# midi_block_R2_0.net
KiCad netlist of a schematic drawn in EAGLE
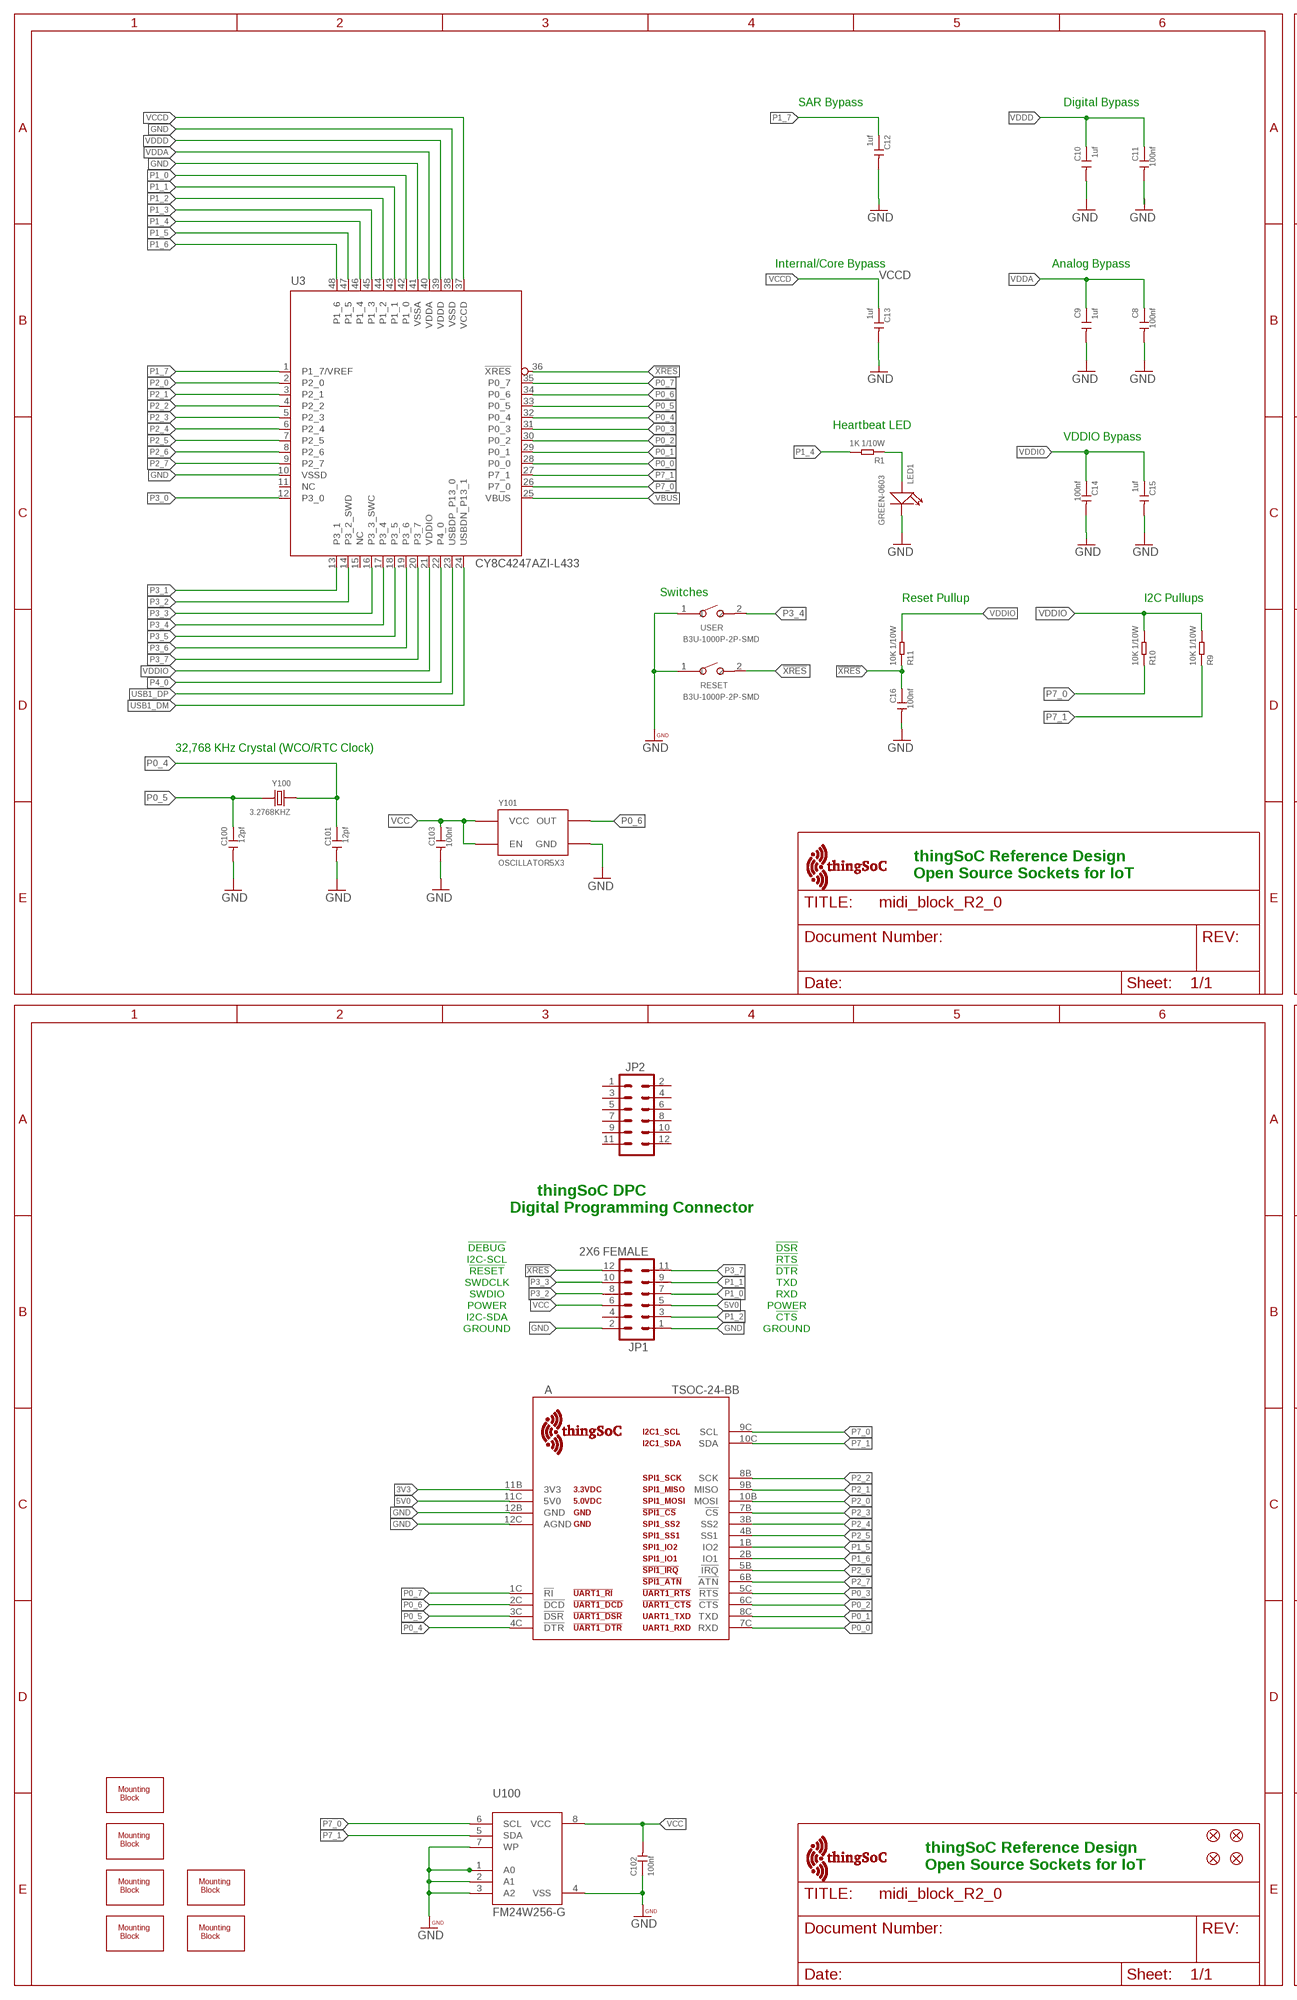
[diagram p0: schematic, sheet 1, part 1 of 2]
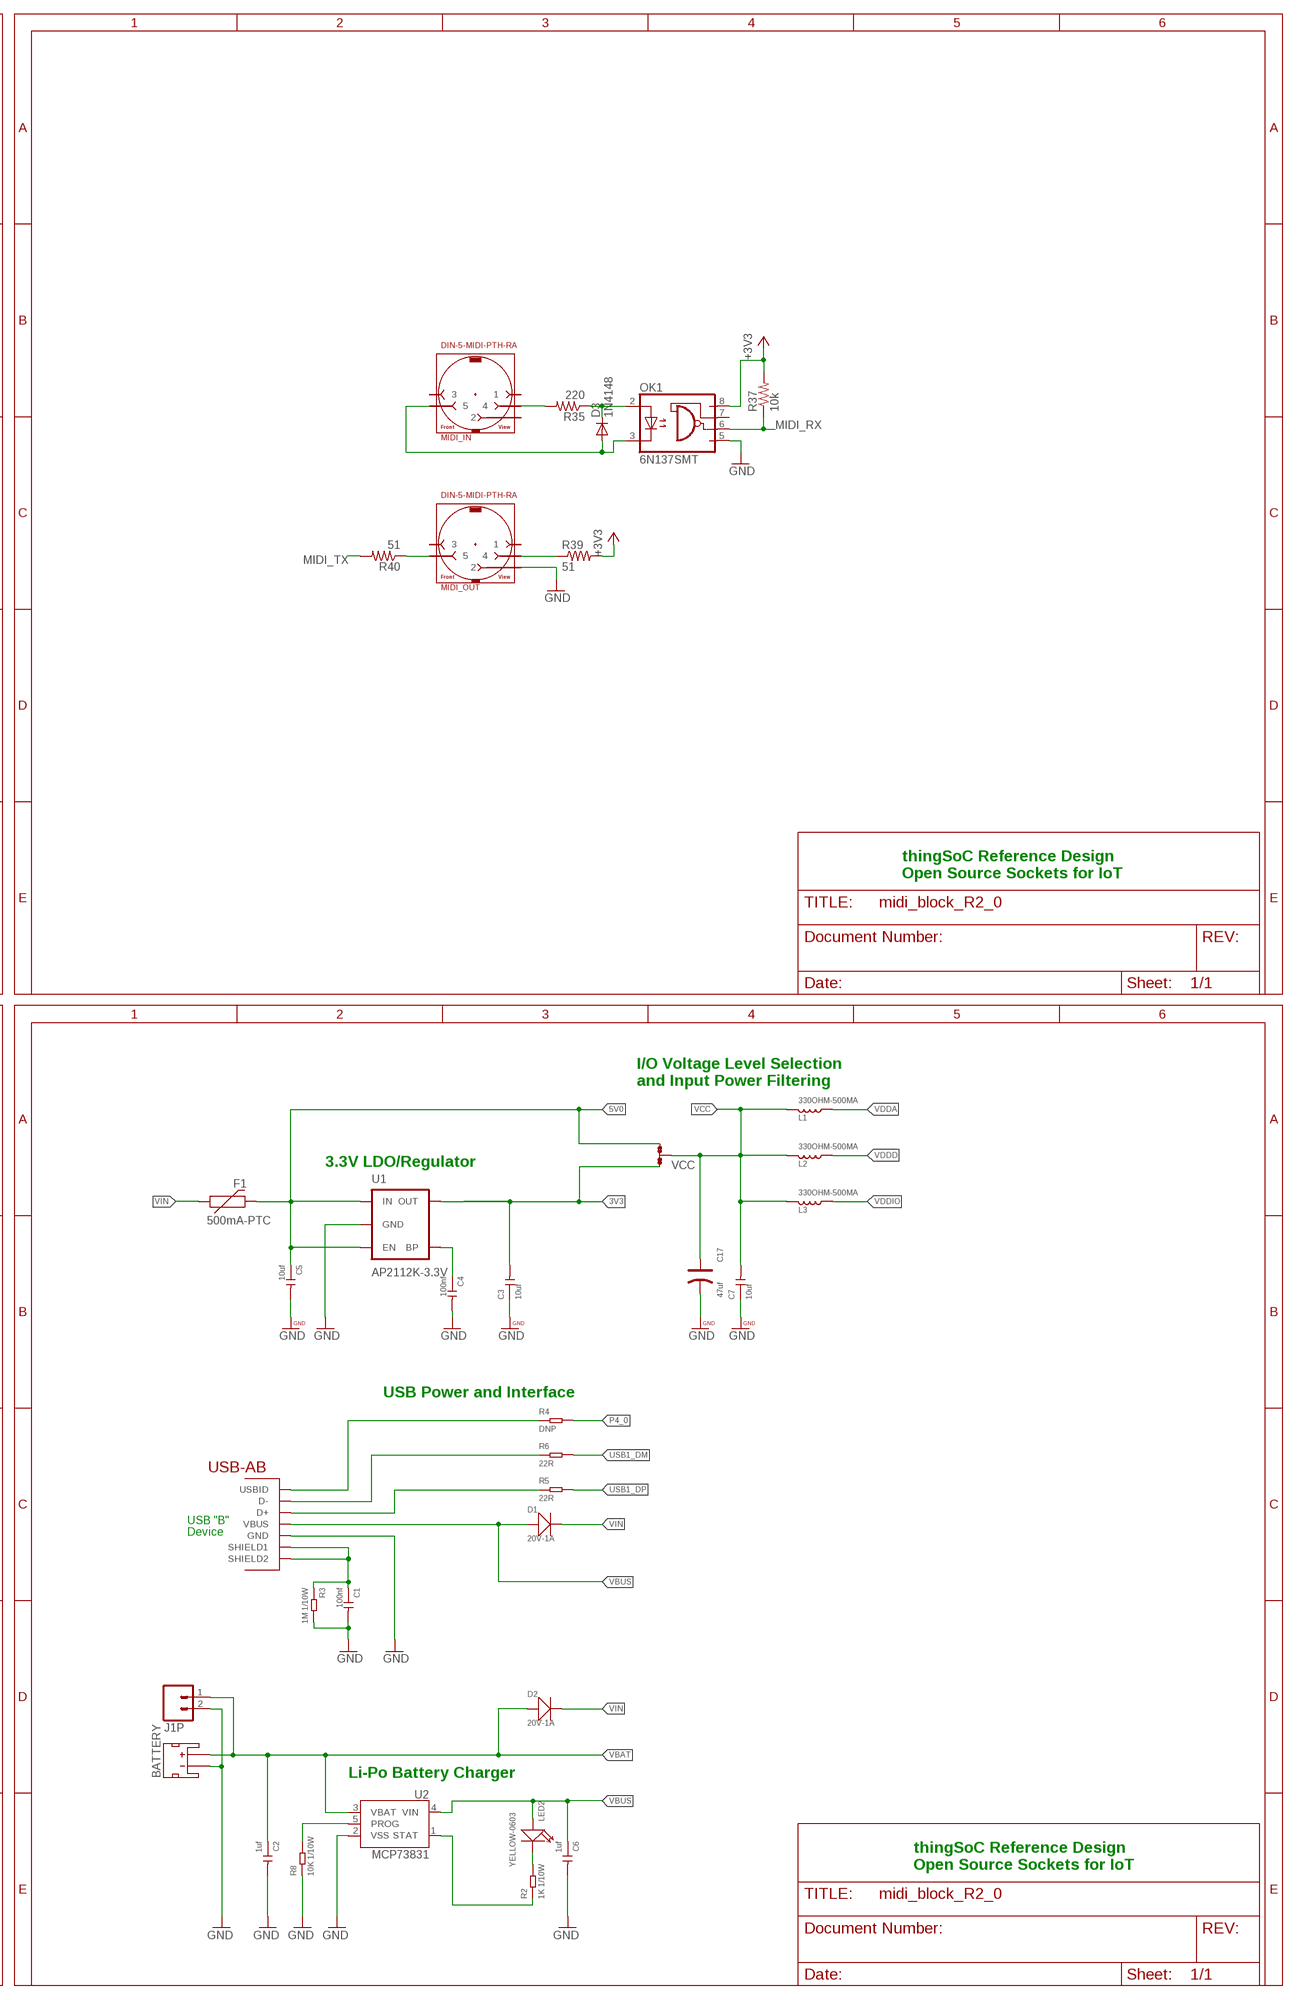
[diagram p1: schematic, sheet 1, part 2 of 2]

(export (version "E")
  (design (tool "Eeschema 10.0.6"))
  (components
    (comp (ref "A")
      (value "TSOC-24-BB")
      (footprint "eagle-import:TSOC-BB-S24")
      (libsource (lib "eagle-import") (part "TSOC-24-BB"))
    )
    (comp (ref "BATTERY")
      (value "JST_2MM_MALE")
      (footprint "eagle-import:JST-2-SMD")
      (libsource (lib "eagle-import") (part "JST_2MM_MALE"))
    )
    (comp (ref "C1")
      (value "100nf")
      (footprint "eagle-import:C0603")
      (fields (field (name "MPN") "CC0603KRX7R9BB104"))
      (libsource (lib "eagle-import") (part "CERAMIC-100NF-50V-10%-X7R(0603)"))
    )
    (comp (ref "C2")
      (value "1uf")
      (footprint "eagle-import:C0603")
      (fields (field (name "MPN") "CC0603KRX7R8BB105"))
      (libsource (lib "eagle-import") (part "CERAMIC-1UF-25V-10%-X7R(0603)"))
    )
    (comp (ref "C3")
      (value "10uf")
      (footprint "eagle-import:C0603")
      (fields (field (name "MPN") "CC0603KRX5R6BB106"))
      (libsource (lib "eagle-import") (part "CERAMIC-10UF-10V-10%-X5R(0603)"))
    )
    (comp (ref "C4")
      (value "100nf")
      (footprint "eagle-import:C0603")
      (fields (field (name "MPN") "CC0603KRX7R9BB104"))
      (libsource (lib "eagle-import") (part "CERAMIC-100NF-50V-10%-X7R(0603)"))
    )
    (comp (ref "C5")
      (value "10uf")
      (footprint "eagle-import:C0603")
      (fields (field (name "MPN") "CC0603KRX5R6BB106"))
      (libsource (lib "eagle-import") (part "CERAMIC-10UF-10V-10%-X5R(0603)"))
    )
    (comp (ref "C6")
      (value "1uf")
      (footprint "eagle-import:C0603")
      (fields (field (name "MPN") "CC0603KRX7R8BB105"))
      (libsource (lib "eagle-import") (part "CERAMIC-1UF-25V-10%-X7R(0603)"))
    )
    (comp (ref "C7")
      (value "10uf")
      (footprint "eagle-import:C0603")
      (fields (field (name "MPN") "CC0603KRX5R6BB106"))
      (libsource (lib "eagle-import") (part "CERAMIC-10UF-10V-10%-X5R(0603)"))
    )
    (comp (ref "C8")
      (value "100nf")
      (footprint "eagle-import:C0603")
      (fields (field (name "MPN") "CC0603KRX7R9BB104"))
      (libsource (lib "eagle-import") (part "CERAMIC-100NF-50V-10%-X7R(0603)"))
    )
    (comp (ref "C9")
      (value "1uf")
      (footprint "eagle-import:C0603")
      (fields (field (name "MPN") "CC0603KRX7R8BB105"))
      (libsource (lib "eagle-import") (part "CERAMIC-1UF-25V-10%-X7R(0603)"))
    )
    (comp (ref "C10")
      (value "1uf")
      (footprint "eagle-import:C0603")
      (fields (field (name "MPN") "CC0603KRX7R8BB105"))
      (libsource (lib "eagle-import") (part "CERAMIC-1UF-25V-10%-X7R(0603)"))
    )
    (comp (ref "C11")
      (value "100nf")
      (footprint "eagle-import:C0603")
      (fields (field (name "MPN") "CC0603KRX7R9BB104"))
      (libsource (lib "eagle-import") (part "CERAMIC-100NF-50V-10%-X7R(0603)"))
    )
    (comp (ref "C12")
      (value "1uf")
      (footprint "eagle-import:C0603")
      (fields (field (name "MPN") "CC0603KRX7R8BB105"))
      (libsource (lib "eagle-import") (part "CERAMIC-1UF-25V-10%-X7R(0603)"))
    )
    (comp (ref "C13")
      (value "1uf")
      (footprint "eagle-import:C0603")
      (fields (field (name "MPN") "CC0603KRX7R8BB105"))
      (libsource (lib "eagle-import") (part "CERAMIC-1UF-25V-10%-X7R(0603)"))
    )
    (comp (ref "C14")
      (value "100nf")
      (footprint "eagle-import:C0603")
      (fields (field (name "MPN") "CC0603KRX7R9BB104"))
      (libsource (lib "eagle-import") (part "CERAMIC-100NF-50V-10%-X7R(0603)"))
    )
    (comp (ref "C15")
      (value "1uf")
      (footprint "eagle-import:C0603")
      (fields (field (name "MPN") "CC0603KRX7R8BB105"))
      (libsource (lib "eagle-import") (part "CERAMIC-1UF-25V-10%-X7R(0603)"))
    )
    (comp (ref "C16")
      (value "100nf")
      (footprint "eagle-import:C0603")
      (fields (field (name "MPN") "CC0603KRX7R9BB104"))
      (libsource (lib "eagle-import") (part "CERAMIC-100NF-50V-10%-X7R(0603)"))
    )
    (comp (ref "C17")
      (value "47uf")
      (footprint "eagle-import:AVX-A")
      (fields (field (name "MPN") "TAJA476*006#NJ"))
      (libsource (lib "eagle-import") (part "TANTALUM-SMD-47UF-6.3V(AVX-A)"))
    )
    (comp (ref "C100")
      (value "12pf")
      (footprint "eagle-import:C0603")
      (fields (field (name "MPN") "CC0603JRNPO9BN120"))
      (libsource (lib "eagle-import") (part "CERAMIC-12PF-50V-5%-NPO(0603)"))
    )
    (comp (ref "C101")
      (value "12pf")
      (footprint "eagle-import:C0603")
      (fields (field (name "MPN") "CC0603JRNPO9BN120"))
      (libsource (lib "eagle-import") (part "CERAMIC-12PF-50V-5%-NPO(0603)"))
    )
    (comp (ref "C102")
      (value "100nf")
      (footprint "eagle-import:C0603")
      (fields (field (name "MPN") "CC0603KRX7R9BB104"))
      (libsource (lib "eagle-import") (part "CERAMIC-100NF-50V-10%-X7R(0603)"))
    )
    (comp (ref "C103")
      (value "100nf")
      (footprint "eagle-import:C0603")
      (fields (field (name "MPN") "CC0603KRX7R9BB104"))
      (libsource (lib "eagle-import") (part "CERAMIC-100NF-50V-10%-X7R(0603)"))
    )
    (comp (ref "D1")
      (value "20V-1A")
      (footprint "eagle-import:SOD-123")
      (fields (field (name "MPN") "B5819W"))
      (libsource (lib "eagle-import") (part "SMD-DIODE-SCHOTTKY-20V-1A(SOD-123)"))
    )
    (comp (ref "D2")
      (value "20V-1A")
      (footprint "eagle-import:SOD-123")
      (fields (field (name "MPN") "B5819W"))
      (libsource (lib "eagle-import") (part "SMD-DIODE-SCHOTTKY-20V-1A(SOD-123)"))
    )
    (comp (ref "D3")
      (value "1N4148")
      (footprint "eagle-import:SOD323-W")
      (libsource (lib "eagle-import") (part "DIODE-SOD323-W"))
    )
    (comp (ref "F1")
      (value "500mA-PTC")
      (footprint "eagle-import:PTC-1206")
      (libsource (lib "eagle-import") (part "PTCSMD"))
    )
    (comp (ref "FID1")
      (value "FIDUCIALUFIDUCIAL")
      (footprint "eagle-import:MICRO-FIDUCIAL")
      (libsource (lib "eagle-import") (part "FIDUCIALUFIDUCIAL"))
    )
    (comp (ref "FID2")
      (value "FIDUCIALUFIDUCIAL")
      (footprint "eagle-import:MICRO-FIDUCIAL")
      (libsource (lib "eagle-import") (part "FIDUCIALUFIDUCIAL"))
    )
    (comp (ref "FID3")
      (value "FIDUCIALUFIDUCIAL")
      (footprint "eagle-import:MICRO-FIDUCIAL")
      (libsource (lib "eagle-import") (part "FIDUCIALUFIDUCIAL"))
    )
    (comp (ref "FID4")
      (value "FIDUCIALUFIDUCIAL")
      (footprint "eagle-import:MICRO-FIDUCIAL")
      (libsource (lib "eagle-import") (part "FIDUCIALUFIDUCIAL"))
    )
    (comp (ref "J1P")
      (value "M02-JST-2-PTH-NO_SILK")
      (footprint "eagle-import:JST-2-PTH-NS")
      (libsource (lib "eagle-import") (part "M02-JST-2-PTH-NO_SILK"))
    )
    (comp (ref "JP1")
      (value "2X6 FEMALE")
      (footprint "eagle-import:2X6")
      (libsource (lib "eagle-import") (part "M06X2PTH_FEMALE"))
    )
    (comp (ref "JP2")
      (value "M06X2FEMALE-SMT")
      (footprint "eagle-import:2X6_SMD")
      (libsource (lib "eagle-import") (part "M06X2FEMALE-SMT"))
    )
    (comp (ref "L1")
      (value "330OHM-500MA")
      (footprint "eagle-import:L0603")
      (fields (field (name "MPN") "BLM18AG121SN1D"))
      (libsource (lib "eagle-import") (part "SMD-FERRITE-CHIP-120-OHM-500MA(0603)"))
    )
    (comp (ref "L2")
      (value "330OHM-500MA")
      (footprint "eagle-import:L0603")
      (fields (field (name "MPN") "BLM18AG121SN1D"))
      (libsource (lib "eagle-import") (part "SMD-FERRITE-CHIP-120-OHM-500MA(0603)"))
    )
    (comp (ref "L3")
      (value "330OHM-500MA")
      (footprint "eagle-import:L0603")
      (fields (field (name "MPN") "BLM18AG121SN1D"))
      (libsource (lib "eagle-import") (part "SMD-FERRITE-CHIP-120-OHM-500MA(0603)"))
    )
    (comp (ref "LED1")
      (value "GREEN-0603")
      (footprint "eagle-import:LED-0603")
      (fields (field (name "MPN") "19-217-G7C-AN1P2-3T"))
      (libsource (lib "eagle-import") (part "SMD-LED-CLEAR-GREEN(0603)"))
    )
    (comp (ref "LED2")
      (value "YELLOW-0603")
      (footprint "eagle-import:LED-0603")
      (fields (field (name "MPN") "19-217-Y5C-AM1N1VY-3T"))
      (libsource (lib "eagle-import") (part "SMD-LED-CLEAR-YELLOW(0603)"))
    )
    (comp (ref "MIDI_IN")
      (value "DIN-5-MIDI-PTH-RA")
      (footprint "eagle-import:DIN-5-PTH-RA-SUPPORT")
      (libsource (lib "eagle-import") (part "DIN-5-MIDI-PTH-RA"))
    )
    (comp (ref "MIDI_OUT")
      (value "DIN-5-MIDI-PTH-RA")
      (footprint "eagle-import:DIN-5-PTH-RA-SUPPORT")
      (libsource (lib "eagle-import") (part "DIN-5-MIDI-PTH-RA"))
    )
    (comp (ref "OK1")
      (value "6N137SMT")
      (footprint "eagle-import:DIL8-SMD")
      (libsource (lib "eagle-import") (part "6N137SMT"))
    )
    (comp (ref "R1")
      (value "1K 1/10W")
      (footprint "eagle-import:R0603")
      (fields (field (name "MPN") "RC0603JR-071KL"))
      (libsource (lib "eagle-import") (part "SMD-RES-1K-5%-1/10W(0603)"))
    )
    (comp (ref "R2")
      (value "1K 1/10W")
      (footprint "eagle-import:R0603")
      (fields (field (name "MPN") "RC0603JR-071KL"))
      (libsource (lib "eagle-import") (part "SMD-RES-1K-5%-1/10W(0603)"))
    )
    (comp (ref "R3")
      (value "1M 1/10W")
      (footprint "eagle-import:R0603")
      (fields (field (name "MPN") "RC0603JR-071ML"))
      (libsource (lib "eagle-import") (part "SMD-RES-1M-5%-1/10W(0603)"))
    )
    (comp (ref "R4")
      (value "DNP")
      (footprint "eagle-import:R0603")
      (fields (field (name "MPN") "RC0603JR-0722RL"))
      (libsource (lib "eagle-import") (part "SMD-RES-22R-5%-1/10W(0603)"))
    )
    (comp (ref "R5")
      (value "22R")
      (footprint "eagle-import:R0603")
      (fields (field (name "MPN") "RC0603JR-0722RL"))
      (libsource (lib "eagle-import") (part "SMD-RES-22R-5%-1/10W(0603)"))
    )
    (comp (ref "R6")
      (value "22R")
      (footprint "eagle-import:R0603")
      (fields (field (name "MPN") "RC0603JR-0722RL"))
      (libsource (lib "eagle-import") (part "SMD-RES-22R-5%-1/10W(0603)"))
    )
    (comp (ref "R8")
      (value "10K 1/10W")
      (footprint "eagle-import:R0603")
      (fields (field (name "MPN") "RC0603JR-0710KL"))
      (libsource (lib "eagle-import") (part "SMD-RES-10K-5%-1/10W(0603)"))
    )
    (comp (ref "R9")
      (value "10K 1/10W")
      (footprint "eagle-import:R0603")
      (fields (field (name "MPN") "RC0603JR-0710KL"))
      (libsource (lib "eagle-import") (part "SMD-RES-10K-5%-1/10W(0603)"))
    )
    (comp (ref "R10")
      (value "10K 1/10W")
      (footprint "eagle-import:R0603")
      (fields (field (name "MPN") "RC0603JR-0710KL"))
      (libsource (lib "eagle-import") (part "SMD-RES-10K-5%-1/10W(0603)"))
    )
    (comp (ref "R11")
      (value "10K 1/10W")
      (footprint "eagle-import:R0603")
      (fields (field (name "MPN") "RC0603JR-0710KL"))
      (libsource (lib "eagle-import") (part "SMD-RES-10K-5%-1/10W(0603)"))
    )
    (comp (ref "R35")
      (value "220")
      (footprint "eagle-import:R0603")
      (libsource (lib "eagle-import") (part "R-US_R0603"))
    )
    (comp (ref "R37")
      (value "10k")
      (footprint "eagle-import:R0603")
      (libsource (lib "eagle-import") (part "R-US_R0603"))
    )
    (comp (ref "R39")
      (value "51")
      (footprint "eagle-import:R0603")
      (libsource (lib "eagle-import") (part "R-US_R0603"))
    )
    (comp (ref "R40")
      (value "51")
      (footprint "eagle-import:R0603")
      (libsource (lib "eagle-import") (part "R-US_R0603"))
    )
    (comp (ref "RESET")
      (value "B3U-1000P-2P-SMD")
      (footprint "eagle-import:SW2-2.6-3.0X2.5X1.2+0.4MM")
      (libsource (lib "eagle-import") (part "SMD-BUTTON(2P-3.0X2.5X1.2+0.4MM)-B3U-1000P-2P-SMD"))
    )
    (comp (ref "U$1")
      (value "PCB-MB-SIDE")
      (footprint "eagle-import:PCB-MB-01-SIDE")
      (libsource (lib "eagle-import") (part "PCB-MB-SIDE"))
    )
    (comp (ref "U$7")
      (value "PCB-MB-SIDE")
      (footprint "eagle-import:PCB-MB-01-SIDE")
      (libsource (lib "eagle-import") (part "PCB-MB-SIDE"))
    )
    (comp (ref "U$8")
      (value "PCB-MB-SIDE")
      (footprint "eagle-import:PCB-MB-01-SIDE")
      (libsource (lib "eagle-import") (part "PCB-MB-SIDE"))
    )
    (comp (ref "U$9")
      (value "PCB-MB-SIDE")
      (footprint "eagle-import:PCB-MB-01-SIDE")
      (libsource (lib "eagle-import") (part "PCB-MB-SIDE"))
    )
    (comp (ref "U$10")
      (value "PCB-MB-SIDE")
      (footprint "eagle-import:PCB-MB-01-SIDE")
      (libsource (lib "eagle-import") (part "PCB-MB-SIDE"))
    )
    (comp (ref "U$11")
      (value "PCB-MB-SIDE")
      (footprint "eagle-import:PCB-MB-01-SIDE")
      (libsource (lib "eagle-import") (part "PCB-MB-SIDE"))
    )
    (comp (ref "U$100")
      (value "TSOC-LOGO-LRG")
      (footprint "eagle-import:TSOC-LOGO-LRG")
      (libsource (lib "eagle-import") (part "TSOC-LOGO-LRG"))
    )
    (comp (ref "U$101")
      (value "TSOC-LOGO-SMALL")
      (footprint "eagle-import:TSOC-LOGO-SML")
      (libsource (lib "eagle-import") (part "TSOC-LOGO-SMALL"))
    )
    (comp (ref "U1")
      (value "AP2112K-3.3V")
      (footprint "eagle-import:SOT23-5")
      (libsource (lib "eagle-import") (part "V_REG_LDOSMD"))
    )
    (comp (ref "U2")
      (value "MCP73831")
      (footprint "eagle-import:SOT23-5")
      (libsource (lib "eagle-import") (part "MCP73831"))
    )
    (comp (ref "U3")
      (value "CY8C4247AZI-L433")
      (footprint "eagle-import:TQFP-7X7-48")
      (libsource (lib "eagle-import") (part "CY8C4247AZI-L433"))
    )
    (comp (ref "U100")
      (value "FM24W256-G")
      (footprint "eagle-import:SO08")
      (libsource (lib "eagle-import") (part "FM24W256-G"))
    )
    (comp (ref "USB")
      (value "USB_AB")
      (footprint "eagle-import:USB-AB-MICRO-SMD")
      (libsource (lib "eagle-import") (part "USB_AB"))
    )
    (comp (ref "USER")
      (value "B3U-1000P-2P-SMD")
      (footprint "eagle-import:SW2-2.6-3.0X2.5X1.2+0.4MM")
      (libsource (lib "eagle-import") (part "SMD-BUTTON(2P-3.0X2.5X1.2+0.4MM)-B3U-1000P-2P-SMD"))
    )
    (comp (ref "VCC")
      (value "JMP-3-1_2")
      (footprint "eagle-import:JMP-3-1_2")
      (libsource (lib "eagle-import") (part "JMP-3-1_2"))
    )
    (comp (ref "Y100")
      (value "3.2768KHZ")
      (footprint "eagle-import:X2-SMD-L2.0X1.2X0.55MM")
      (fields (field (name "MPN") "FC-12M"))
      (libsource (lib "eagle-import") (part "SMD-CRYSTAL-32.768KHZ-12.5PF-20PPM-90K(2P-L2.0X1.2MM)"))
    )
    (comp (ref "Y101")
      (value "OSCILLATOR5X3")
      (footprint "eagle-import:CRYSTAL-SMD-5X3")
      (libsource (lib "eagle-import") (part "OSCILLATOR5X3"))
    )
  )
  (nets
    (net (code "1") (name "+3V3") (class "Default")
      (node (ref "OK1") (pin "8") (pinfunction "VCC_8") (pintype "passive"))
      (node (ref "R37") (pin "2") (pinfunction "2_2") (pintype "passive"))
      (node (ref "R39") (pin "2") (pinfunction "2_2") (pintype "passive"))
    )
    (net (code "2") (name "/MIDI_RX") (class "Default")
      (node (ref "OK1") (pin "6") (pinfunction "VO_6") (pintype "passive"))
      (node (ref "R37") (pin "1") (pinfunction "1_1") (pintype "passive"))
    )
    (net (code "3") (name "/MIDI_TX") (class "Default")
      (node (ref "R40") (pin "2") (pinfunction "2_2") (pintype "passive"))
    )
    (net (code "4") (name "/~{XRES}") (class "Default")
      (node (ref "C16") (pin "1") (pinfunction "1_1") (pintype "passive"))
      (node (ref "JP1") (pin "12") (pinfunction "12_12") (pintype "passive"))
      (node (ref "R11") (pin "1") (pinfunction "1_1") (pintype "passive"))
      (node (ref "RESET") (pin "2") (pinfunction "2_2") (pintype "bidirectional"))
      (node (ref "U3") (pin "36") (pinfunction "~{XRES}_36") (pintype "bidirectional"))
    )
    (net (code "5") (name "3V3") (class "Default")
      (node (ref "A") (pin "11B") (pinfunction "3V3_11B") (pintype "bidirectional"))
      (node (ref "C3") (pin "2") (pinfunction "2_2") (pintype "passive"))
      (node (ref "U1") (pin "5") (pinfunction "OUT_5") (pintype "passive"))
      (node (ref "VCC") (pin "1") (pinfunction "1_1") (pintype "passive"))
    )
    (net (code "6") (name "5V0") (class "Default")
      (node (ref "A") (pin "11C") (pinfunction "5V0_11C") (pintype "bidirectional"))
      (node (ref "C5") (pin "1") (pinfunction "1_1") (pintype "passive"))
      (node (ref "F1") (pin "2") (pinfunction "2_2") (pintype "bidirectional"))
      (node (ref "JP1") (pin "5") (pinfunction "5_5") (pintype "passive"))
      (node (ref "U1") (pin "1") (pinfunction "IN_1") (pintype "input"))
      (node (ref "U1") (pin "3") (pinfunction "EN_3") (pintype "input"))
      (node (ref "VCC") (pin "3") (pinfunction "3_3") (pintype "passive"))
    )
    (net (code "7") (name "GND") (class "Default")
      (node (ref "A") (pin "12B") (pinfunction "GND_12B") (pintype "bidirectional"))
      (node (ref "A") (pin "12C") (pinfunction "AGND_12C") (pintype "bidirectional"))
      (node (ref "BATTERY") (pin "1") (pinfunction "-_1") (pintype "bidirectional"))
      (node (ref "C1") (pin "2") (pinfunction "2_2") (pintype "passive"))
      (node (ref "C10") (pin "2") (pinfunction "2_2") (pintype "passive"))
      (node (ref "C100") (pin "2") (pinfunction "2_2") (pintype "passive"))
      (node (ref "C101") (pin "2") (pinfunction "2_2") (pintype "passive"))
      (node (ref "C102") (pin "1") (pinfunction "1_1") (pintype "passive"))
      (node (ref "C103") (pin "2") (pinfunction "2_2") (pintype "passive"))
      (node (ref "C11") (pin "2") (pinfunction "2_2") (pintype "passive"))
      (node (ref "C12") (pin "2") (pinfunction "2_2") (pintype "passive"))
      (node (ref "C13") (pin "2") (pinfunction "2_2") (pintype "passive"))
      (node (ref "C14") (pin "2") (pinfunction "2_2") (pintype "passive"))
      (node (ref "C15") (pin "2") (pinfunction "2_2") (pintype "passive"))
      (node (ref "C16") (pin "2") (pinfunction "2_2") (pintype "passive"))
      (node (ref "C17") (pin "-") (pinfunction "-_-") (pintype "passive"))
      (node (ref "C2") (pin "2") (pinfunction "2_2") (pintype "passive"))
      (node (ref "C3") (pin "1") (pinfunction "1_1") (pintype "passive"))
      (node (ref "C4") (pin "2") (pinfunction "2_2") (pintype "passive"))
      (node (ref "C5") (pin "2") (pinfunction "2_2") (pintype "passive"))
      (node (ref "C6") (pin "2") (pinfunction "2_2") (pintype "passive"))
      (node (ref "C7") (pin "1") (pinfunction "1_1") (pintype "passive"))
      (node (ref "C8") (pin "2") (pinfunction "2_2") (pintype "passive"))
      (node (ref "C9") (pin "2") (pinfunction "2_2") (pintype "passive"))
      (node (ref "J1P") (pin "2") (pinfunction "2_2") (pintype "passive"))
      (node (ref "JP1") (pin "1") (pinfunction "1_1") (pintype "passive"))
      (node (ref "JP1") (pin "2") (pinfunction "2_2") (pintype "passive"))
      (node (ref "LED1") (pin "-") (pinfunction "-_-") (pintype "passive"))
      (node (ref "MIDI_OUT") (pin "2") (pinfunction "2_2") (pintype "bidirectional"))
      (node (ref "OK1") (pin "5") (pinfunction "GND_5") (pintype "passive"))
      (node (ref "R3") (pin "2") (pinfunction "2_2") (pintype "passive"))
      (node (ref "R8") (pin "1") (pinfunction "1_1") (pintype "passive"))
      (node (ref "RESET") (pin "1") (pinfunction "1_1") (pintype "bidirectional"))
      (node (ref "U1") (pin "2") (pinfunction "GND_2") (pintype "input"))
      (node (ref "U100") (pin "1") (pinfunction "A0_1") (pintype "bidirectional"))
      (node (ref "U100") (pin "2") (pinfunction "A1_2") (pintype "bidirectional"))
      (node (ref "U100") (pin "3") (pinfunction "A2_3") (pintype "bidirectional"))
      (node (ref "U100") (pin "4") (pinfunction "VSS_4") (pintype "power_in"))
      (node (ref "U100") (pin "7") (pinfunction "WP_7") (pintype "bidirectional"))
      (node (ref "U2") (pin "2") (pinfunction "VSS_2") (pintype "power_in"))
      (node (ref "U3") (pin "10") (pinfunction "VSSD_10") (pintype "bidirectional"))
      (node (ref "U3") (pin "38") (pinfunction "VSSD_38") (pintype "bidirectional"))
      (node (ref "U3") (pin "41") (pinfunction "VSSA_41") (pintype "bidirectional"))
      (node (ref "USB") (pin "GND") (pinfunction "GND_GND") (pintype "bidirectional"))
      (node (ref "USER") (pin "1") (pinfunction "1_1") (pintype "bidirectional"))
      (node (ref "Y101") (pin "2") (pinfunction "GND_2") (pintype "bidirectional"))
    )
    (net (code "8") (name "Net-(C1-Pad1)") (class "Default")
      (node (ref "C1") (pin "1") (pinfunction "1_1") (pintype "passive"))
      (node (ref "R3") (pin "1") (pinfunction "1_1") (pintype "passive"))
      (node (ref "USB") (pin "SHIELD1") (pinfunction "SHIELD1_SHIELD1") (pintype "bidirectional"))
      (node (ref "USB") (pin "SHIELD2") (pinfunction "SHIELD2_SHIELD2") (pintype "bidirectional"))
    )
    (net (code "9") (name "Net-(LED1-Pad+)") (class "Default")
      (node (ref "LED1") (pin "+") (pinfunction "+_+") (pintype "passive"))
      (node (ref "R1") (pin "1") (pinfunction "1_1") (pintype "passive"))
    )
    (net (code "10") (name "Net-(LED2-Pad-)") (class "Default")
      (node (ref "LED2") (pin "-") (pinfunction "-_-") (pintype "passive"))
      (node (ref "R2") (pin "2") (pinfunction "2_2") (pintype "passive"))
    )
    (net (code "11") (name "Net-(MIDI_IN-Pad4)") (class "Default")
      (node (ref "MIDI_IN") (pin "4") (pinfunction "4_4") (pintype "bidirectional"))
      (node (ref "R35") (pin "2") (pinfunction "2_2") (pintype "passive"))
    )
    (net (code "12") (name "Net-(MIDI_OUT-Pad4)") (class "Default")
      (node (ref "MIDI_OUT") (pin "4") (pinfunction "4_4") (pintype "bidirectional"))
      (node (ref "R39") (pin "1") (pinfunction "1_1") (pintype "passive"))
    )
    (net (code "13") (name "Net-(MIDI_OUT-Pad5)") (class "Default")
      (node (ref "MIDI_OUT") (pin "5") (pinfunction "5_5") (pintype "bidirectional"))
      (node (ref "R40") (pin "1") (pinfunction "1_1") (pintype "passive"))
    )
    (net (code "14") (name "Net-(OK1-A)") (class "Default")
      (node (ref "D3") (pin "C") (pinfunction "C_C") (pintype "passive"))
      (node (ref "OK1") (pin "2") (pinfunction "A_2") (pintype "passive"))
      (node (ref "R35") (pin "1") (pinfunction "1_1") (pintype "passive"))
    )
    (net (code "15") (name "Net-(OK1-C)") (class "Default")
      (node (ref "D3") (pin "A") (pinfunction "A_A") (pintype "passive"))
      (node (ref "MIDI_IN") (pin "5") (pinfunction "5_5") (pintype "bidirectional"))
      (node (ref "OK1") (pin "3") (pinfunction "C_3") (pintype "passive"))
    )
    (net (code "16") (name "Net-(R5-Pad1)") (class "Default")
      (node (ref "R5") (pin "1") (pinfunction "1_1") (pintype "passive"))
      (node (ref "USB") (pin "D+") (pinfunction "D+_D+") (pintype "bidirectional"))
    )
    (net (code "17") (name "Net-(R6-Pad1)") (class "Default")
      (node (ref "R6") (pin "1") (pinfunction "1_1") (pintype "passive"))
      (node (ref "USB") (pin "D-") (pinfunction "D-_D-") (pintype "bidirectional"))
    )
    (net (code "18") (name "Net-(U1-BP)") (class "Default")
      (node (ref "C4") (pin "1") (pinfunction "1_1") (pintype "passive"))
      (node (ref "U1") (pin "4") (pinfunction "BP_4") (pintype "input"))
    )
    (net (code "19") (name "Net-(U2-PROG)") (class "Default")
      (node (ref "R8") (pin "2") (pinfunction "2_2") (pintype "passive"))
      (node (ref "U2") (pin "5") (pinfunction "PROG_5") (pintype "input"))
    )
    (net (code "20") (name "Net-(U2-STAT)") (class "Default")
      (node (ref "R2") (pin "1") (pinfunction "1_1") (pintype "passive"))
      (node (ref "U2") (pin "1") (pinfunction "STAT_1") (pintype "output"))
    )
    (net (code "21") (name "Net-(USB-USBID)") (class "Default")
      (node (ref "R4") (pin "1") (pinfunction "1_1") (pintype "passive"))
      (node (ref "USB") (pin "ID") (pinfunction "USBID_ID") (pintype "bidirectional"))
    )
    (net (code "22") (name "P0_0") (class "Default")
      (node (ref "A") (pin "7C") (pinfunction "RXD_7C") (pintype "bidirectional"))
      (node (ref "U3") (pin "28") (pinfunction "P0_0_28") (pintype "bidirectional"))
    )
    (net (code "23") (name "P0_1") (class "Default")
      (node (ref "A") (pin "8C") (pinfunction "TXD_8C") (pintype "bidirectional"))
      (node (ref "U3") (pin "29") (pinfunction "P0_1_29") (pintype "bidirectional"))
    )
    (net (code "24") (name "P0_2") (class "Default")
      (node (ref "A") (pin "6C") (pinfunction "~{CTS}_6C") (pintype "bidirectional"))
      (node (ref "U3") (pin "30") (pinfunction "P0_2_30") (pintype "input"))
    )
    (net (code "25") (name "P0_3") (class "Default")
      (node (ref "A") (pin "5C") (pinfunction "~{RTS}_5C") (pintype "bidirectional"))
      (node (ref "U3") (pin "31") (pinfunction "P0_3_31") (pintype "bidirectional"))
    )
    (net (code "26") (name "P0_4") (class "Default")
      (node (ref "A") (pin "4C") (pinfunction "~{DTR}_4C") (pintype "bidirectional"))
      (node (ref "C101") (pin "1") (pinfunction "1_1") (pintype "passive"))
      (node (ref "U3") (pin "32") (pinfunction "P0_4_32") (pintype "bidirectional"))
      (node (ref "Y100") (pin "1") (pinfunction "1_1") (pintype "passive"))
    )
    (net (code "27") (name "P0_5") (class "Default")
      (node (ref "A") (pin "3C") (pinfunction "~{DSR}_3C") (pintype "bidirectional"))
      (node (ref "C100") (pin "1") (pinfunction "1_1") (pintype "passive"))
      (node (ref "U3") (pin "33") (pinfunction "P0_5_33") (pintype "bidirectional"))
      (node (ref "Y100") (pin "2") (pinfunction "2_2") (pintype "passive"))
    )
    (net (code "28") (name "P0_6") (class "Default")
      (node (ref "A") (pin "2C") (pinfunction "~{DCD}_2C") (pintype "bidirectional"))
      (node (ref "U3") (pin "34") (pinfunction "P0_6_34") (pintype "power_in"))
      (node (ref "Y101") (pin "3") (pinfunction "OUT_3") (pintype "bidirectional"))
    )
    (net (code "29") (name "P0_7") (class "Default")
      (node (ref "A") (pin "1C") (pinfunction "~{RI}_1C") (pintype "bidirectional"))
      (node (ref "U3") (pin "35") (pinfunction "P0_7_35") (pintype "bidirectional"))
    )
    (net (code "30") (name "P1_0") (class "Default")
      (node (ref "JP1") (pin "7") (pinfunction "7_7") (pintype "passive"))
      (node (ref "U3") (pin "42") (pinfunction "P1_0_42") (pintype "bidirectional"))
    )
    (net (code "31") (name "P1_1") (class "Default")
      (node (ref "JP1") (pin "9") (pinfunction "9_9") (pintype "passive"))
      (node (ref "U3") (pin "43") (pinfunction "P1_1_43") (pintype "bidirectional"))
    )
    (net (code "32") (name "P1_2") (class "Default")
      (node (ref "JP1") (pin "3") (pinfunction "3_3") (pintype "passive"))
      (node (ref "U3") (pin "44") (pinfunction "P1_2_44") (pintype "power_in"))
    )
    (net (code "33") (name "P1_3") (class "Default")
      (node (ref "U3") (pin "45") (pinfunction "P1_3_45") (pintype "bidirectional"))
    )
    (net (code "34") (name "P1_4") (class "Default")
      (node (ref "R1") (pin "2") (pinfunction "2_2") (pintype "passive"))
      (node (ref "U3") (pin "46") (pinfunction "P1_4_46") (pintype "bidirectional"))
    )
    (net (code "35") (name "P1_5") (class "Default")
      (node (ref "A") (pin "1B") (pinfunction "IO2_1B") (pintype "bidirectional"))
      (node (ref "U3") (pin "47") (pinfunction "P1_5_47") (pintype "bidirectional"))
    )
    (net (code "36") (name "P1_6") (class "Default")
      (node (ref "A") (pin "2B") (pinfunction "IO1_2B") (pintype "bidirectional"))
      (node (ref "U3") (pin "48") (pinfunction "P1_6_48") (pintype "bidirectional"))
    )
    (net (code "37") (name "P1_7") (class "Default")
      (node (ref "C12") (pin "1") (pinfunction "1_1") (pintype "passive"))
      (node (ref "U3") (pin "1") (pinfunction "P1_7/VREF_1") (pintype "bidirectional"))
    )
    (net (code "38") (name "P2_0") (class "Default")
      (node (ref "A") (pin "10B") (pinfunction "MOSI_10B") (pintype "bidirectional"))
      (node (ref "U3") (pin "2") (pinfunction "P2_0_2") (pintype "bidirectional"))
    )
    (net (code "39") (name "P2_1") (class "Default")
      (node (ref "A") (pin "9B") (pinfunction "MISO_9B") (pintype "bidirectional"))
      (node (ref "U3") (pin "3") (pinfunction "P2_1_3") (pintype "bidirectional"))
    )
    (net (code "40") (name "P2_2") (class "Default")
      (node (ref "A") (pin "8B") (pinfunction "SCK_8B") (pintype "bidirectional"))
      (node (ref "U3") (pin "4") (pinfunction "P2_2_4") (pintype "power_in"))
    )
    (net (code "41") (name "P2_3") (class "Default")
      (node (ref "A") (pin "7B") (pinfunction "~{CS}_7B") (pintype "bidirectional"))
      (node (ref "U3") (pin "5") (pinfunction "P2_3_5") (pintype "bidirectional"))
    )
    (net (code "42") (name "P2_4") (class "Default")
      (node (ref "A") (pin "3B") (pinfunction "SS2_3B") (pintype "bidirectional"))
      (node (ref "U3") (pin "6") (pinfunction "P2_4_6") (pintype "bidirectional"))
    )
    (net (code "43") (name "P2_5") (class "Default")
      (node (ref "A") (pin "4B") (pinfunction "SS1_4B") (pintype "bidirectional"))
      (node (ref "U3") (pin "7") (pinfunction "P2_5_7") (pintype "bidirectional"))
    )
    (net (code "44") (name "P2_6") (class "Default")
      (node (ref "A") (pin "5B") (pinfunction "~{IRQ}_5B") (pintype "bidirectional"))
      (node (ref "U3") (pin "8") (pinfunction "P2_6_8") (pintype "power_in"))
    )
    (net (code "45") (name "P2_7") (class "Default")
      (node (ref "A") (pin "6B") (pinfunction "~{ATN}_6B") (pintype "bidirectional"))
      (node (ref "U3") (pin "9") (pinfunction "P2_7_9") (pintype "bidirectional"))
    )
    (net (code "46") (name "P3_0") (class "Default")
      (node (ref "U3") (pin "12") (pinfunction "P3_0_12") (pintype "bidirectional"))
    )
    (net (code "47") (name "P3_1") (class "Default")
      (node (ref "U3") (pin "13") (pinfunction "P3_1_13") (pintype "bidirectional"))
    )
    (net (code "48") (name "P3_2") (class "Default")
      (node (ref "JP1") (pin "8") (pinfunction "8_8") (pintype "passive"))
      (node (ref "U3") (pin "14") (pinfunction "P3_2_SWD_14") (pintype "bidirectional"))
    )
    (net (code "49") (name "P3_3") (class "Default")
      (node (ref "JP1") (pin "10") (pinfunction "10_10") (pintype "passive"))
      (node (ref "U3") (pin "16") (pinfunction "P3_3_SWC_16") (pintype "bidirectional"))
    )
    (net (code "50") (name "P3_4") (class "Default")
      (node (ref "U3") (pin "17") (pinfunction "P3_4_17") (pintype "bidirectional"))
      (node (ref "USER") (pin "2") (pinfunction "2_2") (pintype "bidirectional"))
    )
    (net (code "51") (name "P3_5") (class "Default")
      (node (ref "U3") (pin "18") (pinfunction "P3_5_18") (pintype "bidirectional"))
    )
    (net (code "52") (name "P3_6") (class "Default")
      (node (ref "U3") (pin "19") (pinfunction "P3_6_19") (pintype "power_in"))
    )
    (net (code "53") (name "P3_7") (class "Default")
      (node (ref "JP1") (pin "11") (pinfunction "11_11") (pintype "passive"))
      (node (ref "U3") (pin "20") (pinfunction "P3_7_20") (pintype "bidirectional"))
    )
    (net (code "54") (name "P4_0") (class "Default")
      (node (ref "R4") (pin "2") (pinfunction "2_2") (pintype "passive"))
      (node (ref "U3") (pin "22") (pinfunction "P4_0_22") (pintype "bidirectional"))
    )
    (net (code "55") (name "P7_0") (class "Default")
      (node (ref "A") (pin "9C") (pinfunction "SCL_9C") (pintype "bidirectional"))
      (node (ref "R10") (pin "1") (pinfunction "1_1") (pintype "passive"))
      (node (ref "U100") (pin "6") (pinfunction "SCL_6") (pintype "bidirectional"))
      (node (ref "U3") (pin "26") (pinfunction "P7_0_26") (pintype "bidirectional"))
    )
    (net (code "56") (name "P7_1") (class "Default")
      (node (ref "A") (pin "10C") (pinfunction "SDA_10C") (pintype "bidirectional"))
      (node (ref "R9") (pin "1") (pinfunction "1_1") (pintype "passive"))
      (node (ref "U100") (pin "5") (pinfunction "SDA_5") (pintype "bidirectional"))
      (node (ref "U3") (pin "27") (pinfunction "P7_1_27") (pintype "bidirectional"))
    )
    (net (code "57") (name "USB1_DM") (class "Default")
      (node (ref "R6") (pin "2") (pinfunction "2_2") (pintype "passive"))
      (node (ref "U3") (pin "24") (pinfunction "USBDN_P13_1_24") (pintype "bidirectional"))
    )
    (net (code "58") (name "USB1_DP") (class "Default")
      (node (ref "R5") (pin "2") (pinfunction "2_2") (pintype "passive"))
      (node (ref "U3") (pin "23") (pinfunction "USBDP_P13_0_23") (pintype "bidirectional"))
    )
    (net (code "59") (name "VBAT") (class "Default")
      (node (ref "BATTERY") (pin "2") (pinfunction "+_2") (pintype "bidirectional"))
      (node (ref "C2") (pin "1") (pinfunction "1_1") (pintype "passive"))
      (node (ref "D2") (pin "+") (pinfunction "+_+") (pintype "passive"))
      (node (ref "J1P") (pin "1") (pinfunction "1_1") (pintype "passive"))
      (node (ref "U2") (pin "3") (pinfunction "VBAT_3") (pintype "power_in"))
    )
    (net (code "60") (name "VBUS") (class "Default")
      (node (ref "C6") (pin "1") (pinfunction "1_1") (pintype "passive"))
      (node (ref "D1") (pin "+") (pinfunction "+_+") (pintype "passive"))
      (node (ref "LED2") (pin "+") (pinfunction "+_+") (pintype "passive"))
      (node (ref "U2") (pin "4") (pinfunction "VIN_4") (pintype "power_in"))
      (node (ref "U3") (pin "25") (pinfunction "VBUS_25") (pintype "bidirectional"))
      (node (ref "USB") (pin "VBUS") (pinfunction "VBUS_VBUS") (pintype "bidirectional"))
    )
    (net (code "61") (name "VCC") (class "Default")
      (node (ref "C102") (pin "2") (pinfunction "2_2") (pintype "passive"))
      (node (ref "C103") (pin "1") (pinfunction "1_1") (pintype "passive"))
      (node (ref "C17") (pin "+") (pinfunction "+_+") (pintype "passive"))
      (node (ref "C7") (pin "2") (pinfunction "2_2") (pintype "passive"))
      (node (ref "JP1") (pin "6") (pinfunction "6_6") (pintype "passive"))
      (node (ref "L1") (pin "1") (pinfunction "1_1") (pintype "passive"))
      (node (ref "L2") (pin "1") (pinfunction "1_1") (pintype "passive"))
      (node (ref "L3") (pin "1") (pinfunction "1_1") (pintype "passive"))
      (node (ref "U100") (pin "8") (pinfunction "VCC_8") (pintype "power_in"))
      (node (ref "VCC") (pin "2") (pinfunction "2_2") (pintype "passive"))
      (node (ref "Y101") (pin "1") (pinfunction "EN_1") (pintype "bidirectional"))
      (node (ref "Y101") (pin "4") (pinfunction "VCC_4") (pintype "bidirectional"))
    )
    (net (code "62") (name "VCCD") (class "Default")
      (node (ref "C13") (pin "1") (pinfunction "1_1") (pintype "passive"))
      (node (ref "U3") (pin "37") (pinfunction "VCCD_37") (pintype "bidirectional"))
    )
    (net (code "63") (name "VDDA") (class "Default")
      (node (ref "C8") (pin "1") (pinfunction "1_1") (pintype "passive"))
      (node (ref "C9") (pin "1") (pinfunction "1_1") (pintype "passive"))
      (node (ref "L1") (pin "2") (pinfunction "2_2") (pintype "passive"))
      (node (ref "U3") (pin "40") (pinfunction "VDDA_40") (pintype "bidirectional"))
    )
    (net (code "64") (name "VDDD") (class "Default")
      (node (ref "C10") (pin "1") (pinfunction "1_1") (pintype "passive"))
      (node (ref "C11") (pin "1") (pinfunction "1_1") (pintype "passive"))
      (node (ref "L2") (pin "2") (pinfunction "2_2") (pintype "passive"))
      (node (ref "U3") (pin "39") (pinfunction "VDDD_39") (pintype "bidirectional"))
    )
    (net (code "65") (name "VDDIO") (class "Default")
      (node (ref "C14") (pin "1") (pinfunction "1_1") (pintype "passive"))
      (node (ref "C15") (pin "1") (pinfunction "1_1") (pintype "passive"))
      (node (ref "L3") (pin "2") (pinfunction "2_2") (pintype "passive"))
      (node (ref "R10") (pin "2") (pinfunction "2_2") (pintype "passive"))
      (node (ref "R11") (pin "2") (pinfunction "2_2") (pintype "passive"))
      (node (ref "R9") (pin "2") (pinfunction "2_2") (pintype "passive"))
      (node (ref "U3") (pin "21") (pinfunction "VDDIO_21") (pintype "bidirectional"))
    )
    (net (code "66") (name "VIN") (class "Default")
      (node (ref "D1") (pin "-") (pinfunction "-_-") (pintype "passive"))
      (node (ref "D2") (pin "-") (pinfunction "-_-") (pintype "passive"))
      (node (ref "F1") (pin "1") (pinfunction "1_1") (pintype "bidirectional"))
    )
    (net (code "67") (name "unconnected-(BATTERY-PAD1-PadNC1)") (class "Default")
      (node (ref "BATTERY") (pin "NC1") (pinfunction "PAD1_NC1") (pintype "bidirectional"))
    )
    (net (code "68") (name "unconnected-(BATTERY-PAD2-PadNC2)") (class "Default")
      (node (ref "BATTERY") (pin "NC2") (pinfunction "PAD2_NC2") (pintype "bidirectional"))
    )
    (net (code "69") (name "unconnected-(JP1-Pad4)") (class "Default")
      (node (ref "JP1") (pin "4") (pinfunction "4_4") (pintype "passive"))
    )
    (net (code "70") (name "unconnected-(JP2-Pad1)") (class "Default")
      (node (ref "JP2") (pin "1") (pinfunction "1_1") (pintype "passive"))
    )
    (net (code "71") (name "unconnected-(JP2-Pad2)") (class "Default")
      (node (ref "JP2") (pin "2") (pinfunction "2_2") (pintype "passive"))
    )
    (net (code "72") (name "unconnected-(JP2-Pad3)") (class "Default")
      (node (ref "JP2") (pin "3") (pinfunction "3_3") (pintype "passive"))
    )
    (net (code "73") (name "unconnected-(JP2-Pad4)") (class "Default")
      (node (ref "JP2") (pin "4") (pinfunction "4_4") (pintype "passive"))
    )
    (net (code "74") (name "unconnected-(JP2-Pad5)") (class "Default")
      (node (ref "JP2") (pin "5") (pinfunction "5_5") (pintype "passive"))
    )
    (net (code "75") (name "unconnected-(JP2-Pad6)") (class "Default")
      (node (ref "JP2") (pin "6") (pinfunction "6_6") (pintype "passive"))
    )
    (net (code "76") (name "unconnected-(JP2-Pad7)") (class "Default")
      (node (ref "JP2") (pin "7") (pinfunction "7_7") (pintype "passive"))
    )
    (net (code "77") (name "unconnected-(JP2-Pad8)") (class "Default")
      (node (ref "JP2") (pin "8") (pinfunction "8_8") (pintype "passive"))
    )
    (net (code "78") (name "unconnected-(JP2-Pad9)") (class "Default")
      (node (ref "JP2") (pin "9") (pinfunction "9_9") (pintype "passive"))
    )
    (net (code "79") (name "unconnected-(JP2-Pad10)") (class "Default")
      (node (ref "JP2") (pin "10") (pinfunction "10_10") (pintype "passive"))
    )
    (net (code "80") (name "unconnected-(JP2-Pad11)") (class "Default")
      (node (ref "JP2") (pin "11") (pinfunction "11_11") (pintype "passive"))
    )
    (net (code "81") (name "unconnected-(JP2-Pad12)") (class "Default")
      (node (ref "JP2") (pin "12") (pinfunction "12_12") (pintype "passive"))
    )
    (net (code "82") (name "unconnected-(MIDI_IN-Pad1)") (class "Default")
      (node (ref "MIDI_IN") (pin "1") (pinfunction "1_1") (pintype "bidirectional"))
    )
    (net (code "83") (name "unconnected-(MIDI_IN-Pad2)") (class "Default")
      (node (ref "MIDI_IN") (pin "2") (pinfunction "2_2") (pintype "bidirectional"))
    )
    (net (code "84") (name "unconnected-(MIDI_IN-Pad3)") (class "Default")
      (node (ref "MIDI_IN") (pin "3") (pinfunction "3_3") (pintype "bidirectional"))
    )
    (net (code "85") (name "unconnected-(MIDI_OUT-Pad1)") (class "Default")
      (node (ref "MIDI_OUT") (pin "1") (pinfunction "1_1") (pintype "bidirectional"))
    )
    (net (code "86") (name "unconnected-(MIDI_OUT-Pad3)") (class "Default")
      (node (ref "MIDI_OUT") (pin "3") (pinfunction "3_3") (pintype "bidirectional"))
    )
    (net (code "87") (name "unconnected-(OK1-VE-Pad7)") (class "Default")
      (node (ref "OK1") (pin "7") (pinfunction "VE_7") (pintype "passive"))
    )
    (net (code "88") (name "unconnected-(U3-NC-Pad11)") (class "Default")
      (node (ref "U3") (pin "11") (pinfunction "NC_11") (pintype "bidirectional"))
    )
    (net (code "89") (name "unconnected-(U3-NC-Pad15)") (class "Default")
      (node (ref "U3") (pin "15") (pinfunction "NC_15") (pintype "bidirectional"))
    )
  )
)
